# Nusbio_smd.net
KiCad netlist of a schematic drawn in EAGLE
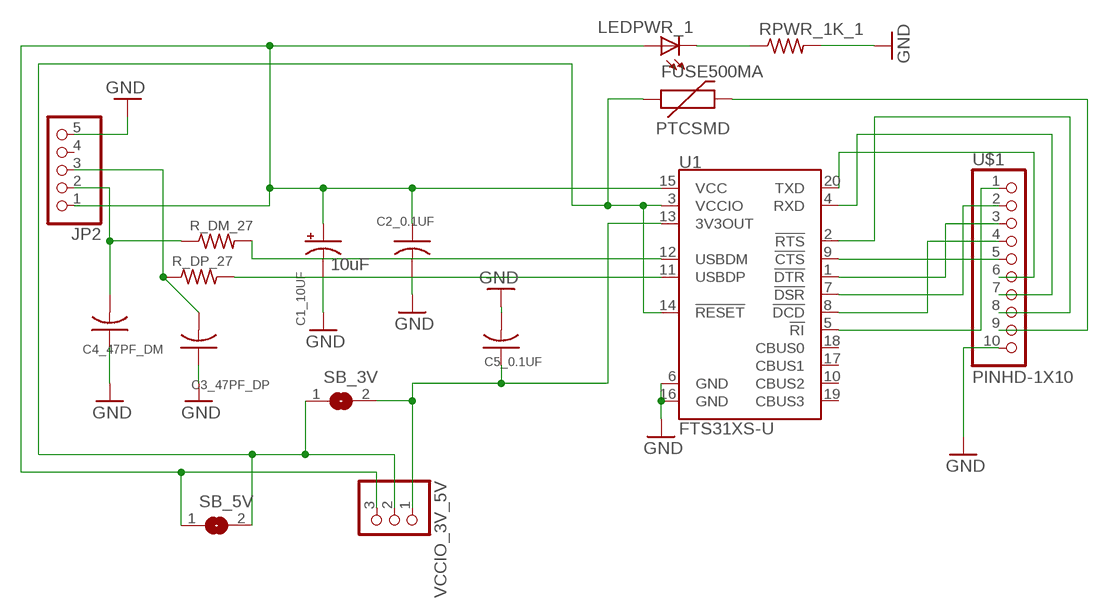
[diagram p0: schematic, sheet 1]

(export (version "E")
  (design (tool "Eeschema 10.0.6"))
  (components
    (comp (ref "C1_10UF")
      (value "10uF")
      (footprint "eagle-import:EIA3216")
      (libsource (lib "eagle-import") (part "10UF-16V-10%(TANT)"))
    )
    (comp (ref "C2_0.1UF")
      (value "C-USC1206")
      (footprint "eagle-import:C1206")
      (libsource (lib "eagle-import") (part "C-USC1206"))
    )
    (comp (ref "C3_47PF_DP")
      (value "C-USC1206")
      (footprint "eagle-import:C1206")
      (libsource (lib "eagle-import") (part "C-USC1206"))
    )
    (comp (ref "C4_47PF_DM")
      (value "C-USC1206")
      (footprint "eagle-import:C1206")
      (libsource (lib "eagle-import") (part "C-USC1206"))
    )
    (comp (ref "C5_0.1UF")
      (value "C-USC1206")
      (footprint "eagle-import:C1206")
      (libsource (lib "eagle-import") (part "C-USC1206"))
    )
    (comp (ref "FUSE500MA")
      (value "PTCSMD")
      (footprint "eagle-import:PTC-1206")
      (libsource (lib "eagle-import") (part "PTCSMD"))
    )
    (comp (ref "JP2")
      (value "PINHD-1X5")
      (footprint "eagle-import:1X05")
      (libsource (lib "eagle-import") (part "PINHD-1X5"))
    )
    (comp (ref "LEDPWR_1")
      (value "LEDCHIPLED_0805")
      (footprint "eagle-import:CHIPLED_0805")
      (libsource (lib "eagle-import") (part "LEDCHIPLED_0805"))
    )
    (comp (ref "RPWR_1K_1")
      (value "R-US_R0805")
      (footprint "eagle-import:R0805")
      (libsource (lib "eagle-import") (part "R-US_R0805"))
    )
    (comp (ref "R_DM_27")
      (value "R-US_R0805")
      (footprint "eagle-import:R0805")
      (libsource (lib "eagle-import") (part "R-US_R0805"))
    )
    (comp (ref "R_DP_27")
      (value "R-US_R0805")
      (footprint "eagle-import:R0805")
      (libsource (lib "eagle-import") (part "R-US_R0805"))
    )
    (comp (ref "SB_3V")
      (value "SOLDERJUMPERREFLOW")
      (footprint "eagle-import:SOLDERJUMPER_REFLOW")
      (libsource (lib "eagle-import") (part "SOLDERJUMPERREFLOW"))
    )
    (comp (ref "SB_5V")
      (value "SOLDERJUMPERREFLOW")
      (footprint "eagle-import:SOLDERJUMPER_REFLOW")
      (libsource (lib "eagle-import") (part "SOLDERJUMPERREFLOW"))
    )
    (comp (ref "U$1")
      (value "PINHD-1X10")
      (footprint "eagle-import:1X10-BIG")
      (libsource (lib "eagle-import") (part "PINHD-1X10"))
    )
    (comp (ref "U1")
      (value "FTS31XS-U")
      (footprint "eagle-import:SSOP20_L")
      (libsource (lib "eagle-import") (part "FT231XS"))
    )
    (comp (ref "VCCIO_3V_5V")
      (value "PINHD-1X3")
      (footprint "eagle-import:1X03")
      (libsource (lib "eagle-import") (part "PINHD-1X3"))
    )
  )
  (nets
    (net (code "1") (name "GND") (class "Default")
      (node (ref "C1_10UF") (pin "C") (pinfunction "-_C") (pintype "passive"))
      (node (ref "C2_0.1UF") (pin "2") (pinfunction "2_2") (pintype "passive"))
      (node (ref "C3_47PF_DP") (pin "1") (pinfunction "1_1") (pintype "passive"))
      (node (ref "C4_47PF_DM") (pin "1") (pinfunction "1_1") (pintype "passive"))
      (node (ref "C5_0.1UF") (pin "2") (pinfunction "2_2") (pintype "passive"))
      (node (ref "JP2") (pin "5") (pinfunction "5_5") (pintype "passive"))
      (node (ref "RPWR_1K_1") (pin "2") (pinfunction "2_2") (pintype "passive"))
      (node (ref "U$1") (pin "10") (pinfunction "10_10") (pintype "passive"))
      (node (ref "U1") (pin "16") (pinfunction "GND_16") (pintype "bidirectional"))
      (node (ref "U1") (pin "6") (pinfunction "GND_6") (pintype "bidirectional"))
    )
    (net (code "2") (name "Net-(C1_10UF-+)") (class "Default")
      (node (ref "C1_10UF") (pin "A") (pinfunction "+_A") (pintype "passive"))
      (node (ref "C2_0.1UF") (pin "1") (pinfunction "1_1") (pintype "passive"))
      (node (ref "JP2") (pin "1") (pinfunction "1_1") (pintype "passive"))
      (node (ref "LEDPWR_1") (pin "A") (pinfunction "A_A") (pintype "passive"))
      (node (ref "SB_5V") (pin "1") (pinfunction "1_1") (pintype "passive"))
      (node (ref "U1") (pin "15") (pinfunction "VCC_15") (pintype "bidirectional"))
      (node (ref "VCCIO_3V_5V") (pin "3") (pinfunction "3_3") (pintype "passive"))
    )
    (net (code "3") (name "Net-(C3_47PF_DP-Pad2)") (class "Default")
      (node (ref "C3_47PF_DP") (pin "2") (pinfunction "2_2") (pintype "passive"))
      (node (ref "JP2") (pin "3") (pinfunction "3_3") (pintype "passive"))
      (node (ref "R_DP_27") (pin "1") (pinfunction "1_1") (pintype "passive"))
    )
    (net (code "4") (name "Net-(C4_47PF_DM-Pad2)") (class "Default")
      (node (ref "C4_47PF_DM") (pin "2") (pinfunction "2_2") (pintype "passive"))
      (node (ref "JP2") (pin "2") (pinfunction "2_2") (pintype "passive"))
      (node (ref "R_DM_27") (pin "1") (pinfunction "1_1") (pintype "passive"))
    )
    (net (code "5") (name "Net-(FUSE500MA-Pad2)") (class "Default")
      (node (ref "FUSE500MA") (pin "2") (pinfunction "2_2") (pintype "bidirectional"))
      (node (ref "U$1") (pin "9") (pinfunction "9_9") (pintype "passive"))
    )
    (net (code "6") (name "Net-(LEDPWR_1-PadC)") (class "Default")
      (node (ref "LEDPWR_1") (pin "C") (pinfunction "C_C") (pintype "passive"))
      (node (ref "RPWR_1K_1") (pin "1") (pinfunction "1_1") (pintype "passive"))
    )
    (net (code "7") (name "Net-(U1-3V3OUT)") (class "Default")
      (node (ref "C5_0.1UF") (pin "1") (pinfunction "1_1") (pintype "passive"))
      (node (ref "SB_3V") (pin "2") (pinfunction "2_2") (pintype "passive"))
      (node (ref "U1") (pin "13") (pinfunction "3V3OUT_13") (pintype "bidirectional"))
      (node (ref "VCCIO_3V_5V") (pin "1") (pinfunction "1_1") (pintype "passive"))
    )
    (net (code "8") (name "Net-(U1-RXD)") (class "Default")
      (node (ref "U$1") (pin "7") (pinfunction "7_7") (pintype "passive"))
      (node (ref "U1") (pin "4") (pinfunction "RXD_4") (pintype "bidirectional"))
    )
    (net (code "9") (name "Net-(U1-TXD)") (class "Default")
      (node (ref "U$1") (pin "6") (pinfunction "6_6") (pintype "passive"))
      (node (ref "U1") (pin "20") (pinfunction "TXD_20") (pintype "bidirectional"))
    )
    (net (code "10") (name "Net-(U1-USBDM)") (class "Default")
      (node (ref "R_DM_27") (pin "2") (pinfunction "2_2") (pintype "passive"))
      (node (ref "U1") (pin "12") (pinfunction "USBDM_12") (pintype "bidirectional"))
    )
    (net (code "11") (name "Net-(U1-USBDP)") (class "Default")
      (node (ref "R_DP_27") (pin "2") (pinfunction "2_2") (pintype "passive"))
      (node (ref "U1") (pin "11") (pinfunction "USBDP_11") (pintype "bidirectional"))
    )
    (net (code "12") (name "Net-(U1-VCCIO)") (class "Default")
      (node (ref "FUSE500MA") (pin "1") (pinfunction "1_1") (pintype "bidirectional"))
      (node (ref "SB_3V") (pin "1") (pinfunction "1_1") (pintype "passive"))
      (node (ref "SB_5V") (pin "2") (pinfunction "2_2") (pintype "passive"))
      (node (ref "U1") (pin "14") (pinfunction "~{RESET}_14") (pintype "bidirectional"))
      (node (ref "U1") (pin "3") (pinfunction "VCCIO_3") (pintype "bidirectional"))
      (node (ref "VCCIO_3V_5V") (pin "2") (pinfunction "2_2") (pintype "passive"))
    )
    (net (code "13") (name "Net-(U1-~{CTS})") (class "Default")
      (node (ref "U$1") (pin "5") (pinfunction "5_5") (pintype "passive"))
      (node (ref "U1") (pin "9") (pinfunction "~{CTS}_9") (pintype "bidirectional"))
    )
    (net (code "14") (name "Net-(U1-~{DCD})") (class "Default")
      (node (ref "U$1") (pin "4") (pinfunction "4_4") (pintype "passive"))
      (node (ref "U1") (pin "8") (pinfunction "~{DCD}_8") (pintype "bidirectional"))
    )
    (net (code "15") (name "Net-(U1-~{DSR})") (class "Default")
      (node (ref "U$1") (pin "2") (pinfunction "2_2") (pintype "passive"))
      (node (ref "U1") (pin "7") (pinfunction "~{DSR}_7") (pintype "bidirectional"))
    )
    (net (code "16") (name "Net-(U1-~{DTR})") (class "Default")
      (node (ref "U$1") (pin "3") (pinfunction "3_3") (pintype "passive"))
      (node (ref "U1") (pin "1") (pinfunction "~{DTR}_1") (pintype "bidirectional"))
    )
    (net (code "17") (name "Net-(U1-~{RI})") (class "Default")
      (node (ref "U$1") (pin "1") (pinfunction "1_1") (pintype "passive"))
      (node (ref "U1") (pin "5") (pinfunction "~{RI}_5") (pintype "bidirectional"))
    )
    (net (code "18") (name "Net-(U1-~{RTS})") (class "Default")
      (node (ref "U$1") (pin "8") (pinfunction "8_8") (pintype "passive"))
      (node (ref "U1") (pin "2") (pinfunction "~{RTS}_2") (pintype "bidirectional"))
    )
    (net (code "19") (name "unconnected-(JP2-Pad4)") (class "Default")
      (node (ref "JP2") (pin "4") (pinfunction "4_4") (pintype "passive"))
    )
    (net (code "20") (name "unconnected-(U1-CBUS0-Pad18)") (class "Default")
      (node (ref "U1") (pin "18") (pinfunction "CBUS0_18") (pintype "bidirectional"))
    )
    (net (code "21") (name "unconnected-(U1-CBUS1-Pad17)") (class "Default")
      (node (ref "U1") (pin "17") (pinfunction "CBUS1_17") (pintype "bidirectional"))
    )
    (net (code "22") (name "unconnected-(U1-CBUS2-Pad10)") (class "Default")
      (node (ref "U1") (pin "10") (pinfunction "CBUS2_10") (pintype "bidirectional"))
    )
    (net (code "23") (name "unconnected-(U1-CBUS3-Pad19)") (class "Default")
      (node (ref "U1") (pin "19") (pinfunction "CBUS3_19") (pintype "bidirectional"))
    )
  )
)
